# BJTSOT343_DCBias.net
KiCad netlist of a schematic drawn in Altium Designer
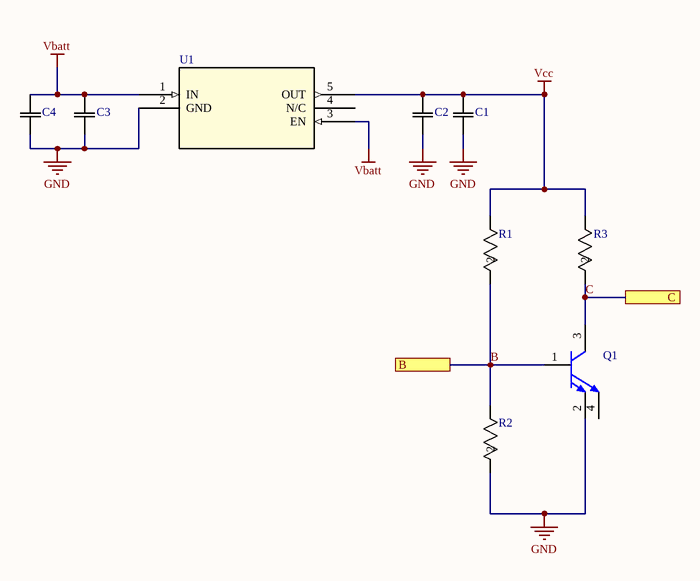
[diagram p0: BJTSOT343_DCBias.SchDoc]

(export (version "E")
  (design (tool "Eeschema 10.0.6"))
  (components
    (comp (ref "C1")
      (value "~")
      (footprint "YAG_CC0402")
      (description "No Description Available")
      (fields
        (field (name "MANUFACTURER_PART_NUMBER") "CC0402KRX7R9BB103")
        (field (name "COPYRIGHT") "Copyright (C) 2018 Accelerated Designs. All rights reserved")
      )
      (libsource (lib "0402Capacitor_Yageo") (part "CC0402KRX7R9BB10"))
    )
    (comp (ref "C2")
      (value "~")
      (footprint "YAG_CC0402")
      (description "No Description Available")
      (fields
        (field (name "MANUFACTURER_PART_NUMBER") "CC0402KRX7R9BB103")
        (field (name "COPYRIGHT") "Copyright (C) 2018 Accelerated Designs. All rights reserved")
      )
      (libsource (lib "0402Capacitor_Yageo") (part "CC0402KRX7R9BB10"))
    )
    (comp (ref "C3")
      (value "~")
      (footprint "YAG_CC0402")
      (description "No Description Available")
      (fields
        (field (name "MANUFACTURER_PART_NUMBER") "CC0402KRX7R9BB103")
        (field (name "COPYRIGHT") "Copyright (C) 2018 Accelerated Designs. All rights reserved")
      )
      (libsource (lib "0402Capacitor_Yageo") (part "CC0402KRX7R9BB10"))
    )
    (comp (ref "C4")
      (value "~")
      (footprint "YAG_CC0402")
      (description "No Description Available")
      (fields
        (field (name "MANUFACTURER_PART_NUMBER") "CC0402KRX7R9BB103")
        (field (name "COPYRIGHT") "Copyright (C) 2018 Accelerated Designs. All rights reserved")
      )
      (libsource (lib "0402Capacitor_Yageo") (part "CC0402KRX7R9BB10"))
    )
    (comp (ref "Q1")
      (value "~")
      (footprint "INF-SOT343_V")
      (fields (field (name "MANUFACTURER") "Infineon") (field (name "PARTNUMBER") "BFP720"))
      (libsource (lib "Infineon_RFBJT_SOT343") (part "BFP720"))
    )
    (comp (ref "R1")
      (value "~")
      (footprint "RC0402N")
      (description "No Description Available")
      (fields
        (field (name "MANUFACTURER_PART_NUMBER") "RC0402JR-070RL")
        (field (name "COPYRIGHT") "Copyright (C) 2018 Accelerated Designs. All rights reserved")
      )
      (libsource (lib "Resistor0402Yageo") (part "RC0402JR-070RL"))
    )
    (comp (ref "R2")
      (value "~")
      (footprint "RC0402N")
      (description "No Description Available")
      (fields
        (field (name "MANUFACTURER_PART_NUMBER") "RC0402JR-070RL")
        (field (name "COPYRIGHT") "Copyright (C) 2018 Accelerated Designs. All rights reserved")
      )
      (libsource (lib "Resistor0402Yageo") (part "RC0402JR-070RL"))
    )
    (comp (ref "R3")
      (value "~")
      (footprint "RC0402N")
      (description "No Description Available")
      (fields
        (field (name "MANUFACTURER_PART_NUMBER") "RC0402JR-070RL")
        (field (name "COPYRIGHT") "Copyright (C) 2018 Accelerated Designs. All rights reserved")
      )
      (libsource (lib "Resistor0402Yageo") (part "RC0402JR-070RL"))
    )
    (comp (ref "U1")
      (value "~")
      (footprint "DBV5")
      (description "No Description Available")
      (fields
        (field (name "MANUFACTURER_PART_NUMBER") "LP5907MFX-3.3/NOPB")
        (field (name "COPYRIGHT") "Copyright (C) 2018 Accelerated Designs. All rights reserved")
      )
      (libsource (lib "TI_LDO_3V3_SOT325") (part "LP5907MFX-3.3/NO"))
    )
  )
  (nets
    (net (code "1") (name "/B") (class "Default")
      (node (ref "Q1") (pin "1") (pinfunction "B_1") (pintype "passive"))
      (node (ref "R1") (pin "2") (pinfunction "2_2") (pintype "passive"))
      (node (ref "R2") (pin "1") (pinfunction "1_1") (pintype "passive"))
    )
    (net (code "2") (name "/C") (class "Default")
      (node (ref "Q1") (pin "3") (pinfunction "C_3") (pintype "passive"))
      (node (ref "R3") (pin "2") (pinfunction "2_2") (pintype "passive"))
    )
    (net (code "3") (name "GND") (class "Default")
      (node (ref "C1") (pin "1") (pinfunction "1_1") (pintype "passive"))
      (node (ref "C2") (pin "1") (pinfunction "1_1") (pintype "passive"))
      (node (ref "C3") (pin "1") (pinfunction "1_1") (pintype "passive"))
      (node (ref "C4") (pin "1") (pinfunction "1_1") (pintype "passive"))
      (node (ref "Q1") (pin "2") (pinfunction "E_2") (pintype "passive"))
      (node (ref "R2") (pin "2") (pinfunction "2_2") (pintype "passive"))
      (node (ref "U1") (pin "2") (pinfunction "GND_2") (pintype "power_in"))
    )
    (net (code "4") (name "Vbatt") (class "Default")
      (node (ref "C3") (pin "2") (pinfunction "2_2") (pintype "passive"))
      (node (ref "C4") (pin "2") (pinfunction "2_2") (pintype "passive"))
      (node (ref "U1") (pin "1") (pinfunction "IN_1") (pintype "input"))
      (node (ref "U1") (pin "3") (pinfunction "EN_3") (pintype "input"))
    )
    (net (code "5") (name "Vcc") (class "Default")
      (node (ref "C1") (pin "2") (pinfunction "2_2") (pintype "passive"))
      (node (ref "C2") (pin "2") (pinfunction "2_2") (pintype "passive"))
      (node (ref "R1") (pin "1") (pinfunction "1_1") (pintype "passive"))
      (node (ref "R3") (pin "1") (pinfunction "1_1") (pintype "passive"))
      (node (ref "U1") (pin "5") (pinfunction "OUT_5") (pintype "output"))
    )
    (net (code "6") (name "unconnected-(Q1-E-Pad4)") (class "Default")
      (node (ref "Q1") (pin "4") (pinfunction "E_4") (pintype "passive"))
    )
    (net (code "7") (name "unconnected-(U1-N{slash}C-Pad4)") (class "Default")
      (node (ref "U1") (pin "4") (pinfunction "N/C_4") (pintype "passive"))
    )
  )
)
